# Power.net
KiCad netlist of a schematic drawn in Altium Designer
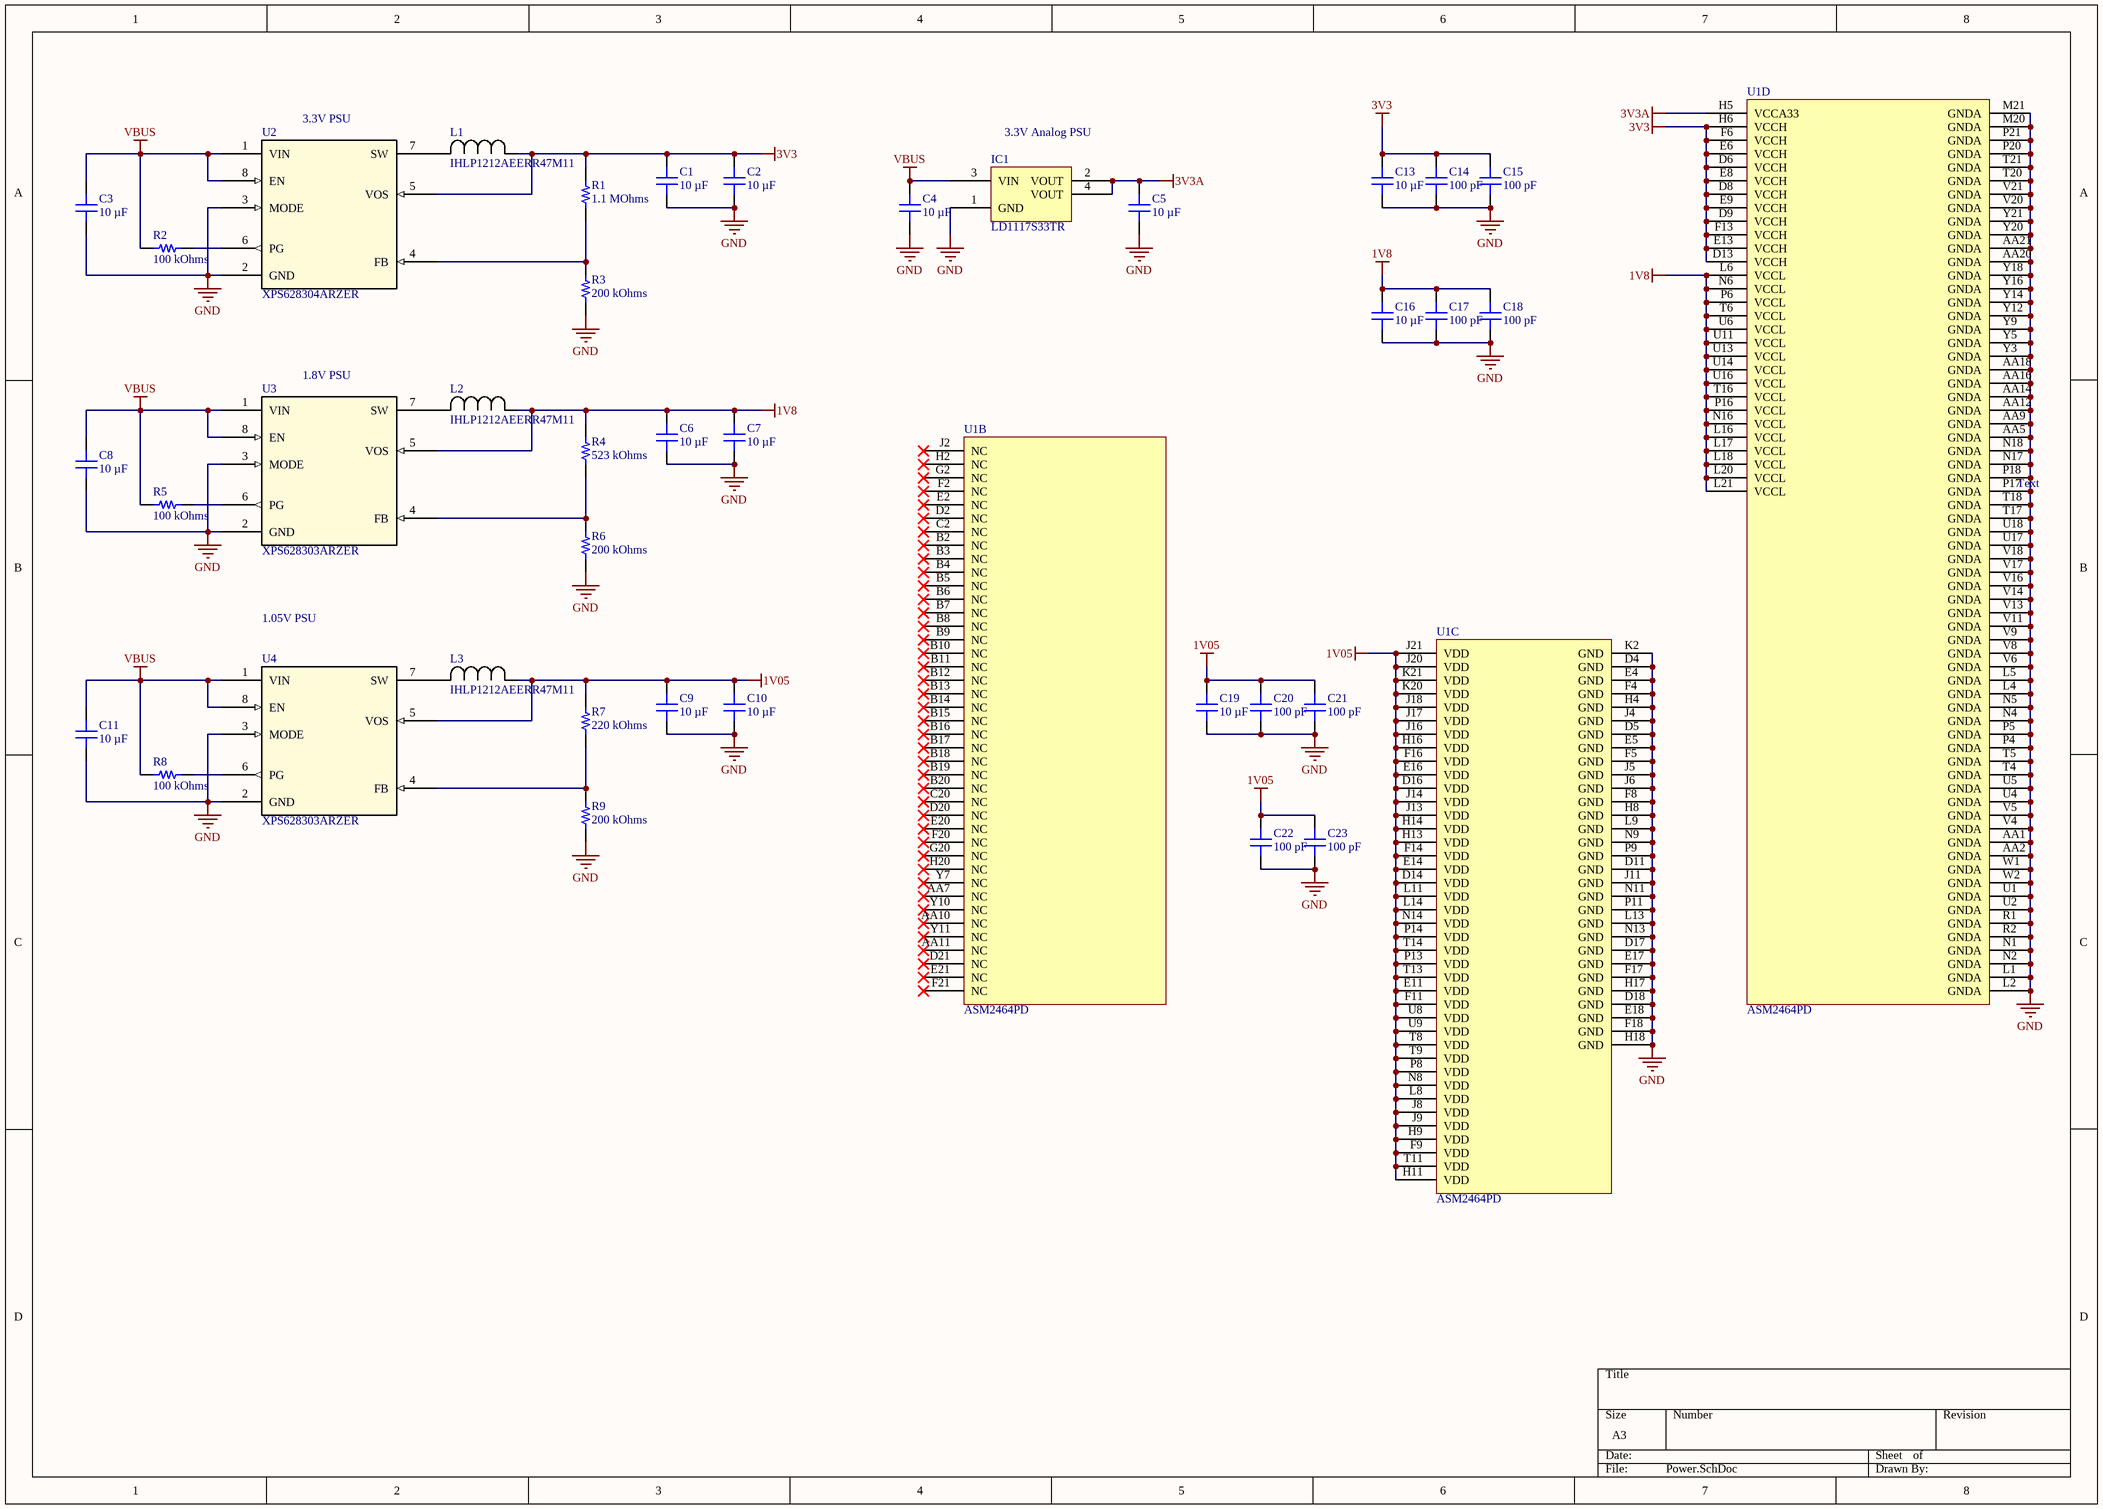
[diagram p0: Power.SchDoc]

(export (version "E")
  (design (tool "Eeschema 10.0.6"))
  (components
    (comp (ref "C1")
      (value "10 µF")
      (footprint "CAP 0805_2012")
      (description "CAP CER 10UF 16V X5R 0805")
      (fields
        (field (name "PART NUMBER") "GRM21BR61C106ME15L")
        (field (name "MANUFACTURER") "Murata Electronics")
      )
      (libsource (lib "Celestial Altium Library - altium_library") (part "Capacitor"))
    )
    (comp (ref "C2")
      (value "10 µF")
      (footprint "CAP 0805_2012")
      (description "CAP CER 10UF 16V X5R 0805")
      (fields
        (field (name "PART NUMBER") "GRM21BR61C106ME15L")
        (field (name "MANUFACTURER") "Murata Electronics")
      )
      (libsource (lib "Celestial Altium Library - altium_library") (part "Capacitor"))
    )
    (comp (ref "C3")
      (value "10 µF")
      (footprint "CAP 0805_2012")
      (description "CAP CER 10UF 16V X5R 0805")
      (fields
        (field (name "PART NUMBER") "GRM21BR61C106ME15L")
        (field (name "MANUFACTURER") "Murata Electronics")
      )
      (libsource (lib "Celestial Altium Library - altium_library") (part "Capacitor"))
    )
    (comp (ref "C4")
      (value "10 µF")
      (footprint "CAP 0805_2012")
      (description "CAP CER 10UF 16V X5R 0805")
      (fields
        (field (name "PART NUMBER") "GRM21BR61C106ME15L")
        (field (name "MANUFACTURER") "Murata Electronics")
      )
      (libsource (lib "Celestial Altium Library - altium_library") (part "Capacitor"))
    )
    (comp (ref "C5")
      (value "10 µF")
      (footprint "CAP 0805_2012")
      (description "CAP CER 10UF 16V X5R 0805")
      (fields
        (field (name "PART NUMBER") "GRM21BR61C106ME15L")
        (field (name "MANUFACTURER") "Murata Electronics")
      )
      (libsource (lib "Celestial Altium Library - altium_library") (part "Capacitor"))
    )
    (comp (ref "C6")
      (value "10 µF")
      (footprint "CAP 0805_2012")
      (description "CAP CER 10UF 16V X5R 0805")
      (fields
        (field (name "PART NUMBER") "GRM21BR61C106ME15L")
        (field (name "MANUFACTURER") "Murata Electronics")
      )
      (libsource (lib "Celestial Altium Library - altium_library") (part "Capacitor"))
    )
    (comp (ref "C7")
      (value "10 µF")
      (footprint "CAP 0805_2012")
      (description "CAP CER 10UF 16V X5R 0805")
      (fields
        (field (name "PART NUMBER") "GRM21BR61C106ME15L")
        (field (name "MANUFACTURER") "Murata Electronics")
      )
      (libsource (lib "Celestial Altium Library - altium_library") (part "Capacitor"))
    )
    (comp (ref "C8")
      (value "10 µF")
      (footprint "CAP 0805_2012")
      (description "CAP CER 10UF 16V X5R 0805")
      (fields
        (field (name "PART NUMBER") "GRM21BR61C106ME15L")
        (field (name "MANUFACTURER") "Murata Electronics")
      )
      (libsource (lib "Celestial Altium Library - altium_library") (part "Capacitor"))
    )
    (comp (ref "C9")
      (value "10 µF")
      (footprint "CAP 0805_2012")
      (description "CAP CER 10UF 16V X5R 0805")
      (fields
        (field (name "PART NUMBER") "GRM21BR61C106ME15L")
        (field (name "MANUFACTURER") "Murata Electronics")
      )
      (libsource (lib "Celestial Altium Library - altium_library") (part "Capacitor"))
    )
    (comp (ref "C10")
      (value "10 µF")
      (footprint "CAP 0805_2012")
      (description "CAP CER 10UF 16V X5R 0805")
      (fields
        (field (name "PART NUMBER") "GRM21BR61C106ME15L")
        (field (name "MANUFACTURER") "Murata Electronics")
      )
      (libsource (lib "Celestial Altium Library - altium_library") (part "Capacitor"))
    )
    (comp (ref "C11")
      (value "10 µF")
      (footprint "CAP 0805_2012")
      (description "CAP CER 10UF 16V X5R 0805")
      (fields
        (field (name "PART NUMBER") "GRM21BR61C106ME15L")
        (field (name "MANUFACTURER") "Murata Electronics")
      )
      (libsource (lib "Celestial Altium Library - altium_library") (part "Capacitor"))
    )
    (comp (ref "C13")
      (value "10 µF")
      (footprint "CAP 0805_2012")
      (description "CAP CER 10UF 16V X5R 0805")
      (fields
        (field (name "PART NUMBER") "GRM21BR61C106ME15L")
        (field (name "MANUFACTURER") "Murata Electronics")
      )
      (libsource (lib "Celestial Altium Library - altium_library") (part "Capacitor"))
    )
    (comp (ref "C14")
      (value "100 pF")
      (footprint "CAP 0603_1608")
      (description "CAP CER 100PF 100V X8G 0603")
      (fields
        (field (name "PART NUMBER") "GCM1885G2A101JA16D")
        (field (name "MANUFACTURER") "Murata Electronics")
      )
      (libsource (lib "Celestial Altium Library - altium_library") (part "Capacitor"))
    )
    (comp (ref "C15")
      (value "100 pF")
      (footprint "CAP 0603_1608")
      (description "CAP CER 100PF 100V X8G 0603")
      (fields
        (field (name "PART NUMBER") "GCM1885G2A101JA16D")
        (field (name "MANUFACTURER") "Murata Electronics")
      )
      (libsource (lib "Celestial Altium Library - altium_library") (part "Capacitor"))
    )
    (comp (ref "C16")
      (value "10 µF")
      (footprint "CAP 0805_2012")
      (description "CAP CER 10UF 16V X5R 0805")
      (fields
        (field (name "PART NUMBER") "GRM21BR61C106ME15L")
        (field (name "MANUFACTURER") "Murata Electronics")
      )
      (libsource (lib "Celestial Altium Library - altium_library") (part "Capacitor"))
    )
    (comp (ref "C17")
      (value "100 pF")
      (footprint "CAP 0603_1608")
      (description "CAP CER 100PF 100V X8G 0603")
      (fields
        (field (name "PART NUMBER") "GCM1885G2A101JA16D")
        (field (name "MANUFACTURER") "Murata Electronics")
      )
      (libsource (lib "Celestial Altium Library - altium_library") (part "Capacitor"))
    )
    (comp (ref "C18")
      (value "100 pF")
      (footprint "CAP 0603_1608")
      (description "CAP CER 100PF 100V X8G 0603")
      (fields
        (field (name "PART NUMBER") "GCM1885G2A101JA16D")
        (field (name "MANUFACTURER") "Murata Electronics")
      )
      (libsource (lib "Celestial Altium Library - altium_library") (part "Capacitor"))
    )
    (comp (ref "C19")
      (value "10 µF")
      (footprint "CAP 0805_2012")
      (description "CAP CER 10UF 16V X5R 0805")
      (fields
        (field (name "PART NUMBER") "GRM21BR61C106ME15L")
        (field (name "MANUFACTURER") "Murata Electronics")
      )
      (libsource (lib "Celestial Altium Library - altium_library") (part "Capacitor"))
    )
    (comp (ref "C20")
      (value "100 pF")
      (footprint "CAP 0603_1608")
      (description "CAP CER 100PF 100V X8G 0603")
      (fields
        (field (name "PART NUMBER") "GCM1885G2A101JA16D")
        (field (name "MANUFACTURER") "Murata Electronics")
      )
      (libsource (lib "Celestial Altium Library - altium_library") (part "Capacitor"))
    )
    (comp (ref "C21")
      (value "100 pF")
      (footprint "CAP 0603_1608")
      (description "CAP CER 100PF 100V X8G 0603")
      (fields
        (field (name "PART NUMBER") "GCM1885G2A101JA16D")
        (field (name "MANUFACTURER") "Murata Electronics")
      )
      (libsource (lib "Celestial Altium Library - altium_library") (part "Capacitor"))
    )
    (comp (ref "C22")
      (value "100 pF")
      (footprint "CAP 0603_1608")
      (description "CAP CER 100PF 100V X8G 0603")
      (fields
        (field (name "PART NUMBER") "GCM1885G2A101JA16D")
        (field (name "MANUFACTURER") "Murata Electronics")
      )
      (libsource (lib "Celestial Altium Library - altium_library") (part "Capacitor"))
    )
    (comp (ref "C23")
      (value "100 pF")
      (footprint "CAP 0603_1608")
      (description "CAP CER 100PF 100V X8G 0603")
      (fields
        (field (name "PART NUMBER") "GCM1885G2A101JA16D")
        (field (name "MANUFACTURER") "Murata Electronics")
      )
      (libsource (lib "Celestial Altium Library - altium_library") (part "Capacitor"))
    )
    (comp (ref "IC1")
      (value "LD1117S33TR")
      (footprint "ST SOT-223")
      (description "IC REG LINEAR 3.3V 800MA SOT223")
      (fields (field (name "MANUFACTURER") "STMicroelectronics"))
      (libsource (lib "Celestial Altium Library - altium_library") (part "ST LD1117"))
    )
    (comp (ref "L1")
      (value "IHLP1212AEERR47M11")
      (footprint "IND_IHLP-1212AE_VIS")
      (description "No Description Available")
      (libsource (lib "IHLP1212AEERR47M11") (part "IHLP1212AEERR47M11"))
    )
    (comp (ref "L2")
      (value "IHLP1212AEERR47M11")
      (footprint "IND_IHLP-1212AE_VIS")
      (description "No Description Available")
      (libsource (lib "IHLP1212AEERR47M11") (part "IHLP1212AEERR47M11"))
    )
    (comp (ref "L3")
      (value "IHLP1212AEERR47M11")
      (footprint "IND_IHLP-1212AE_VIS")
      (description "No Description Available")
      (libsource (lib "IHLP1212AEERR47M11") (part "IHLP1212AEERR47M11"))
    )
    (comp (ref "R1")
      (value "1.1 MOhms")
      (footprint "RES 0805_2012")
      (description "RES SMD 1.1M OHM 5% 1/8W 0805")
      (fields
        (field (name "PART NUMBER") "ERJ-6GEYJ115V")
        (field (name "MANUFACTURER") "Panasonic Electronic Components")
      )
      (libsource (lib "Celestial Altium Library - altium_library") (part "Resistor"))
    )
    (comp (ref "R2")
      (value "100 kOhms")
      (footprint "RES 0805_2012")
      (description "RES SMD 100K OHM 1% 1/8W 0805")
      (fields (field (name "PART NUMBER") "CRCW0805100KFKEA") (field (name "MANUFACTURER") "Vishay Dale"))
      (libsource (lib "Celestial Altium Library - altium_library") (part "Resistor"))
    )
    (comp (ref "R3")
      (value "200 kOhms")
      (footprint "RES 0805_2012")
      (description "RES SMD 200K OHM 5% 1/8W 0805")
      (fields
        (field (name "PART NUMBER") "ERJ-6GEYJ204V")
        (field (name "MANUFACTURER") "Panasonic Electronic Components")
      )
      (libsource (lib "Celestial Altium Library - altium_library") (part "Resistor"))
    )
    (comp (ref "R4")
      (value "523 kOhms")
      (footprint "RES 0805_2012")
      (description "RES SMD 523K OHM 1% 1/8W 0805")
      (fields
        (field (name "PART NUMBER") "ERJ-6ENF5233V")
        (field (name "MANUFACTURER") "Panasonic Electronic Components")
      )
      (libsource (lib "Celestial Altium Library - altium_library") (part "Resistor"))
    )
    (comp (ref "R5")
      (value "100 kOhms")
      (footprint "RES 0805_2012")
      (description "RES SMD 100K OHM 1% 1/8W 0805")
      (fields (field (name "PART NUMBER") "CRCW0805100KFKEA") (field (name "MANUFACTURER") "Vishay Dale"))
      (libsource (lib "Celestial Altium Library - altium_library") (part "Resistor"))
    )
    (comp (ref "R6")
      (value "200 kOhms")
      (footprint "RES 0805_2012")
      (description "RES SMD 200K OHM 5% 1/8W 0805")
      (fields
        (field (name "PART NUMBER") "ERJ-6GEYJ204V")
        (field (name "MANUFACTURER") "Panasonic Electronic Components")
      )
      (libsource (lib "Celestial Altium Library - altium_library") (part "Resistor"))
    )
    (comp (ref "R7")
      (value "220 kOhms")
      (footprint "RES 0805_2012")
      (description "RES SMD 220K OHM 5% 1/8W 0805")
      (fields
        (field (name "PART NUMBER") "ERJ-6GEYJ224V")
        (field (name "MANUFACTURER") "Panasonic Electronic Components")
      )
      (libsource (lib "Celestial Altium Library - altium_library") (part "Resistor"))
    )
    (comp (ref "R8")
      (value "100 kOhms")
      (footprint "RES 0805_2012")
      (description "RES SMD 100K OHM 1% 1/8W 0805")
      (fields (field (name "PART NUMBER") "CRCW0805100KFKEA") (field (name "MANUFACTURER") "Vishay Dale"))
      (libsource (lib "Celestial Altium Library - altium_library") (part "Resistor"))
    )
    (comp (ref "R9")
      (value "200 kOhms")
      (footprint "RES 0805_2012")
      (description "RES SMD 200K OHM 5% 1/8W 0805")
      (fields
        (field (name "PART NUMBER") "ERJ-6GEYJ204V")
        (field (name "MANUFACTURER") "Panasonic Electronic Components")
      )
      (libsource (lib "Celestial Altium Library - altium_library") (part "Resistor"))
    )
    (comp (ref "U1")
      (value "ASM2464PD")
      (footprint "BGA273C46P21X21_1000X1000X98_2")
      (libsource (lib " JS") (part "ASM2464PD"))
    )
    (comp (ref "U2")
      (value "XPS628304ARZER")
      (footprint "WQFN-HR8_RZE_TEX")
      (description "No Description Available")
      (libsource (lib "XPS628303ARZER") (part "XPS628304ARZER"))
    )
    (comp (ref "U3")
      (value "XPS628303ARZER")
      (footprint "WQFN-HR8_RZE_TEX")
      (description "No Description Available")
      (libsource (lib "XPS628303ARZER") (part "XPS628303ARZER"))
    )
    (comp (ref "U4")
      (value "XPS628303ARZER")
      (footprint "WQFN-HR8_RZE_TEX")
      (description "No Description Available")
      (libsource (lib "XPS628303ARZER") (part "XPS628303ARZER"))
    )
  )
  (nets
    (net (code "1") (name "1V05") (class "Default")
      (node (ref "C10") (pin "2") (pinfunction "2_2") (pintype "passive"))
      (node (ref "C19") (pin "2") (pinfunction "2_2") (pintype "passive"))
      (node (ref "C20") (pin "2") (pinfunction "2_2") (pintype "passive"))
      (node (ref "C21") (pin "2") (pinfunction "2_2") (pintype "passive"))
      (node (ref "C22") (pin "2") (pinfunction "2_2") (pintype "passive"))
      (node (ref "C23") (pin "2") (pinfunction "2_2") (pintype "passive"))
      (node (ref "C9") (pin "2") (pinfunction "2_2") (pintype "passive"))
      (node (ref "L3") (pin "1") (pinfunction "1_1") (pintype "passive"))
      (node (ref "R7") (pin "2") (pinfunction "2_2") (pintype "passive"))
      (node (ref "U1") (pin "D14") (pinfunction "VDD_D14") (pintype "power_in"))
      (node (ref "U1") (pin "D16") (pinfunction "VDD_D16") (pintype "power_in"))
      (node (ref "U1") (pin "E11") (pinfunction "VDD_E11") (pintype "power_in"))
      (node (ref "U1") (pin "E14") (pinfunction "VDD_E14") (pintype "power_in"))
      (node (ref "U1") (pin "E16") (pinfunction "VDD_E16") (pintype "power_in"))
      (node (ref "U1") (pin "F11") (pinfunction "VDD_F11") (pintype "power_in"))
      (node (ref "U1") (pin "F14") (pinfunction "VDD_F14") (pintype "power_in"))
      (node (ref "U1") (pin "F16") (pinfunction "VDD_F16") (pintype "power_in"))
      (node (ref "U1") (pin "F9") (pinfunction "VDD_F9") (pintype "power_in"))
      (node (ref "U1") (pin "H11") (pinfunction "VDD_H11") (pintype "power_in"))
      (node (ref "U1") (pin "H13") (pinfunction "VDD_H13") (pintype "power_in"))
      (node (ref "U1") (pin "H14") (pinfunction "VDD_H14") (pintype "power_in"))
      (node (ref "U1") (pin "H16") (pinfunction "VDD_H16") (pintype "power_in"))
      (node (ref "U1") (pin "H9") (pinfunction "VDD_H9") (pintype "power_in"))
      (node (ref "U1") (pin "J13") (pinfunction "VDD_J13") (pintype "power_in"))
      (node (ref "U1") (pin "J14") (pinfunction "VDD_J14") (pintype "power_in"))
      (node (ref "U1") (pin "J16") (pinfunction "VDD_J16") (pintype "power_in"))
      (node (ref "U1") (pin "J17") (pinfunction "VDD_J17") (pintype "power_in"))
      (node (ref "U1") (pin "J18") (pinfunction "VDD_J18") (pintype "power_in"))
      (node (ref "U1") (pin "J20") (pinfunction "VDD_J20") (pintype "power_in"))
      (node (ref "U1") (pin "J21") (pinfunction "VDD_J21") (pintype "power_in"))
      (node (ref "U1") (pin "J8") (pinfunction "VDD_J8") (pintype "power_in"))
      (node (ref "U1") (pin "J9") (pinfunction "VDD_J9") (pintype "power_in"))
      (node (ref "U1") (pin "K20") (pinfunction "VDD_K20") (pintype "power_in"))
      (node (ref "U1") (pin "K21") (pinfunction "VDD_K21") (pintype "power_in"))
      (node (ref "U1") (pin "L11") (pinfunction "VDD_L11") (pintype "power_in"))
      (node (ref "U1") (pin "L14") (pinfunction "VDD_L14") (pintype "power_in"))
      (node (ref "U1") (pin "L8") (pinfunction "VDD_L8") (pintype "power_in"))
      (node (ref "U1") (pin "N14") (pinfunction "VDD_N14") (pintype "power_in"))
      (node (ref "U1") (pin "N8") (pinfunction "VDD_N8") (pintype "power_in"))
      (node (ref "U1") (pin "P13") (pinfunction "VDD_P13") (pintype "power_in"))
      (node (ref "U1") (pin "P14") (pinfunction "VDD_P14") (pintype "power_in"))
      (node (ref "U1") (pin "P8") (pinfunction "VDD_P8") (pintype "power_in"))
      (node (ref "U1") (pin "T11") (pinfunction "VDD_T11") (pintype "power_in"))
      (node (ref "U1") (pin "T13") (pinfunction "VDD_T13") (pintype "power_in"))
      (node (ref "U1") (pin "T14") (pinfunction "VDD_T14") (pintype "power_in"))
      (node (ref "U1") (pin "T8") (pinfunction "VDD_T8") (pintype "power_in"))
      (node (ref "U1") (pin "T9") (pinfunction "VDD_T9") (pintype "power_in"))
      (node (ref "U1") (pin "U8") (pinfunction "VDD_U8") (pintype "power_in"))
      (node (ref "U1") (pin "U9") (pinfunction "VDD_U9") (pintype "power_in"))
      (node (ref "U4") (pin "5") (pinfunction "VOS_5") (pintype "input"))
    )
    (net (code "2") (name "1V8") (class "Default")
      (node (ref "C16") (pin "2") (pinfunction "2_2") (pintype "passive"))
      (node (ref "C17") (pin "2") (pinfunction "2_2") (pintype "passive"))
      (node (ref "C18") (pin "2") (pinfunction "2_2") (pintype "passive"))
      (node (ref "C6") (pin "2") (pinfunction "2_2") (pintype "passive"))
      (node (ref "C7") (pin "2") (pinfunction "2_2") (pintype "passive"))
      (node (ref "L2") (pin "1") (pinfunction "1_1") (pintype "passive"))
      (node (ref "R4") (pin "2") (pinfunction "2_2") (pintype "passive"))
      (node (ref "U1") (pin "L16") (pinfunction "VCCL_L16") (pintype "power_in"))
      (node (ref "U1") (pin "L17") (pinfunction "VCCL_L17") (pintype "power_in"))
      (node (ref "U1") (pin "L18") (pinfunction "VCCL_L18") (pintype "power_in"))
      (node (ref "U1") (pin "L20") (pinfunction "VCCL_L20") (pintype "power_in"))
      (node (ref "U1") (pin "L21") (pinfunction "VCCL_L21") (pintype "power_in"))
      (node (ref "U1") (pin "L6") (pinfunction "VCCL_L6") (pintype "power_in"))
      (node (ref "U1") (pin "N16") (pinfunction "VCCL_N16") (pintype "power_in"))
      (node (ref "U1") (pin "N6") (pinfunction "VCCL_N6") (pintype "power_in"))
      (node (ref "U1") (pin "P16") (pinfunction "VCCL_P16") (pintype "power_in"))
      (node (ref "U1") (pin "P6") (pinfunction "VCCL_P6") (pintype "power_in"))
      (node (ref "U1") (pin "T16") (pinfunction "VCCL_T16") (pintype "power_in"))
      (node (ref "U1") (pin "T6") (pinfunction "VCCL_T6") (pintype "power_in"))
      (node (ref "U1") (pin "U11") (pinfunction "VCCL_U11") (pintype "power_in"))
      (node (ref "U1") (pin "U13") (pinfunction "VCCL_U13") (pintype "power_in"))
      (node (ref "U1") (pin "U14") (pinfunction "VCCL_U14") (pintype "power_in"))
      (node (ref "U1") (pin "U16") (pinfunction "VCCL_U16") (pintype "power_in"))
      (node (ref "U1") (pin "U6") (pinfunction "VCCL_U6") (pintype "power_in"))
      (node (ref "U3") (pin "5") (pinfunction "VOS_5") (pintype "input"))
    )
    (net (code "3") (name "3V3") (class "Default")
      (node (ref "C1") (pin "2") (pinfunction "2_2") (pintype "passive"))
      (node (ref "C13") (pin "2") (pinfunction "2_2") (pintype "passive"))
      (node (ref "C14") (pin "2") (pinfunction "2_2") (pintype "passive"))
      (node (ref "C15") (pin "2") (pinfunction "2_2") (pintype "passive"))
      (node (ref "C2") (pin "2") (pinfunction "2_2") (pintype "passive"))
      (node (ref "L1") (pin "1") (pinfunction "1_1") (pintype "passive"))
      (node (ref "R1") (pin "2") (pinfunction "2_2") (pintype "passive"))
      (node (ref "U1") (pin "D13") (pinfunction "VCCH_D13") (pintype "power_in"))
      (node (ref "U1") (pin "D6") (pinfunction "VCCH_D6") (pintype "power_in"))
      (node (ref "U1") (pin "D8") (pinfunction "VCCH_D8") (pintype "power_in"))
      (node (ref "U1") (pin "D9") (pinfunction "VCCH_D9") (pintype "power_in"))
      (node (ref "U1") (pin "E13") (pinfunction "VCCH_E13") (pintype "power_in"))
      (node (ref "U1") (pin "E6") (pinfunction "VCCH_E6") (pintype "power_in"))
      (node (ref "U1") (pin "E8") (pinfunction "VCCH_E8") (pintype "power_in"))
      (node (ref "U1") (pin "E9") (pinfunction "VCCH_E9") (pintype "power_in"))
      (node (ref "U1") (pin "F13") (pinfunction "VCCH_F13") (pintype "power_in"))
      (node (ref "U1") (pin "F6") (pinfunction "VCCH_F6") (pintype "power_in"))
      (node (ref "U1") (pin "H6") (pinfunction "VCCH_H6") (pintype "power_in"))
      (node (ref "U2") (pin "5") (pinfunction "VOS_5") (pintype "input"))
    )
    (net (code "4") (name "3V3A") (class "Default")
      (node (ref "C5") (pin "2") (pinfunction "2_2") (pintype "passive"))
      (node (ref "IC1") (pin "2") (pinfunction "VOUT_2") (pintype "passive"))
      (node (ref "IC1") (pin "4") (pinfunction "VOUT_4") (pintype "passive"))
      (node (ref "U1") (pin "H5") (pinfunction "VCCA33_H5") (pintype "power_in"))
    )
    (net (code "5") (name "GND") (class "Default")
      (node (ref "C1") (pin "1") (pinfunction "1_1") (pintype "passive"))
      (node (ref "C10") (pin "1") (pinfunction "1_1") (pintype "passive"))
      (node (ref "C11") (pin "1") (pinfunction "1_1") (pintype "passive"))
      (node (ref "C13") (pin "1") (pinfunction "1_1") (pintype "passive"))
      (node (ref "C14") (pin "1") (pinfunction "1_1") (pintype "passive"))
      (node (ref "C15") (pin "1") (pinfunction "1_1") (pintype "passive"))
      (node (ref "C16") (pin "1") (pinfunction "1_1") (pintype "passive"))
      (node (ref "C17") (pin "1") (pinfunction "1_1") (pintype "passive"))
      (node (ref "C18") (pin "1") (pinfunction "1_1") (pintype "passive"))
      (node (ref "C19") (pin "1") (pinfunction "1_1") (pintype "passive"))
      (node (ref "C2") (pin "1") (pinfunction "1_1") (pintype "passive"))
      (node (ref "C20") (pin "1") (pinfunction "1_1") (pintype "passive"))
      (node (ref "C21") (pin "1") (pinfunction "1_1") (pintype "passive"))
      (node (ref "C22") (pin "1") (pinfunction "1_1") (pintype "passive"))
      (node (ref "C23") (pin "1") (pinfunction "1_1") (pintype "passive"))
      (node (ref "C3") (pin "1") (pinfunction "1_1") (pintype "passive"))
      (node (ref "C4") (pin "1") (pinfunction "1_1") (pintype "passive"))
      (node (ref "C5") (pin "1") (pinfunction "1_1") (pintype "passive"))
      (node (ref "C6") (pin "1") (pinfunction "1_1") (pintype "passive"))
      (node (ref "C7") (pin "1") (pinfunction "1_1") (pintype "passive"))
      (node (ref "C8") (pin "1") (pinfunction "1_1") (pintype "passive"))
      (node (ref "C9") (pin "1") (pinfunction "1_1") (pintype "passive"))
      (node (ref "IC1") (pin "1") (pinfunction "GND_1") (pintype "passive"))
      (node (ref "R3") (pin "1") (pinfunction "1_1") (pintype "passive"))
      (node (ref "R6") (pin "1") (pinfunction "1_1") (pintype "passive"))
      (node (ref "R9") (pin "1") (pinfunction "1_1") (pintype "passive"))
      (node (ref "U1") (pin "AA1") (pinfunction "GNDA_AA1") (pintype "power_in"))
      (node (ref "U1") (pin "AA12") (pinfunction "GNDA_AA12") (pintype "power_in"))
      (node (ref "U1") (pin "AA14") (pinfunction "GNDA_AA14") (pintype "power_in"))
      (node (ref "U1") (pin "AA16") (pinfunction "GNDA_AA16") (pintype "power_in"))
      (node (ref "U1") (pin "AA18") (pinfunction "GNDA_AA18") (pintype "power_in"))
      (node (ref "U1") (pin "AA2") (pinfunction "GNDA_AA2") (pintype "power_in"))
      (node (ref "U1") (pin "AA20") (pinfunction "GNDA_AA20") (pintype "power_in"))
      (node (ref "U1") (pin "AA21") (pinfunction "GNDA_AA21") (pintype "power_in"))
      (node (ref "U1") (pin "AA5") (pinfunction "GNDA_AA5") (pintype "power_in"))
      (node (ref "U1") (pin "AA9") (pinfunction "GNDA_AA9") (pintype "power_in"))
      (node (ref "U1") (pin "D11") (pinfunction "GND_D11") (pintype "power_in"))
      (node (ref "U1") (pin "D17") (pinfunction "GND_D17") (pintype "power_in"))
      (node (ref "U1") (pin "D18") (pinfunction "GND_D18") (pintype "power_in"))
      (node (ref "U1") (pin "D4") (pinfunction "GND_D4") (pintype "power_in"))
      (node (ref "U1") (pin "D5") (pinfunction "GND_D5") (pintype "power_in"))
      (node (ref "U1") (pin "E17") (pinfunction "GND_E17") (pintype "power_in"))
      (node (ref "U1") (pin "E18") (pinfunction "GND_E18") (pintype "power_in"))
      (node (ref "U1") (pin "E4") (pinfunction "GND_E4") (pintype "power_in"))
      (node (ref "U1") (pin "E5") (pinfunction "GND_E5") (pintype "power_in"))
      (node (ref "U1") (pin "F17") (pinfunction "GND_F17") (pintype "power_in"))
      (node (ref "U1") (pin "F18") (pinfunction "GND_F18") (pintype "power_in"))
      (node (ref "U1") (pin "F4") (pinfunction "GND_F4") (pintype "power_in"))
      (node (ref "U1") (pin "F5") (pinfunction "GND_F5") (pintype "power_in"))
      (node (ref "U1") (pin "F8") (pinfunction "GND_F8") (pintype "power_in"))
      (node (ref "U1") (pin "H17") (pinfunction "GND_H17") (pintype "power_in"))
      (node (ref "U1") (pin "H18") (pinfunction "GND_H18") (pintype "power_in"))
      (node (ref "U1") (pin "H4") (pinfunction "GND_H4") (pintype "power_in"))
      (node (ref "U1") (pin "H8") (pinfunction "GND_H8") (pintype "power_in"))
      (node (ref "U1") (pin "J11") (pinfunction "GND_J11") (pintype "power_in"))
      (node (ref "U1") (pin "J4") (pinfunction "GND_J4") (pintype "power_in"))
      (node (ref "U1") (pin "J5") (pinfunction "GND_J5") (pintype "power_in"))
      (node (ref "U1") (pin "J6") (pinfunction "GND_J6") (pintype "power_in"))
      (node (ref "U1") (pin "K2") (pinfunction "GND_K2") (pintype "power_in"))
      (node (ref "U1") (pin "L1") (pinfunction "GNDA_L1") (pintype "power_in"))
      (node (ref "U1") (pin "L13") (pinfunction "GND_L13") (pintype "power_in"))
      (node (ref "U1") (pin "L2") (pinfunction "GNDA_L2") (pintype "power_in"))
      (node (ref "U1") (pin "L4") (pinfunction "GNDA_L4") (pintype "power_in"))
      (node (ref "U1") (pin "L5") (pinfunction "GNDA_L5") (pintype "power_in"))
      (node (ref "U1") (pin "L9") (pinfunction "GND_L9") (pintype "power_in"))
      (node (ref "U1") (pin "M20") (pinfunction "GNDA_M20") (pintype "power_in"))
      (node (ref "U1") (pin "M21") (pinfunction "GNDA_M21") (pintype "power_in"))
      (node (ref "U1") (pin "N1") (pinfunction "GNDA_N1") (pintype "power_in"))
      (node (ref "U1") (pin "N11") (pinfunction "GND_N11") (pintype "power_in"))
      (node (ref "U1") (pin "N13") (pinfunction "GND_N13") (pintype "power_in"))
      (node (ref "U1") (pin "N17") (pinfunction "GNDA_N17") (pintype "power_in"))
      (node (ref "U1") (pin "N18") (pinfunction "GNDA_N18") (pintype "power_in"))
      (node (ref "U1") (pin "N2") (pinfunction "GNDA_N2") (pintype "power_in"))
      (node (ref "U1") (pin "N4") (pinfunction "GNDA_N4") (pintype "power_in"))
      (node (ref "U1") (pin "N5") (pinfunction "GNDA_N5") (pintype "power_in"))
      (node (ref "U1") (pin "N9") (pinfunction "GND_N9") (pintype "power_in"))
      (node (ref "U1") (pin "P11") (pinfunction "GND_P11") (pintype "power_in"))
      (node (ref "U1") (pin "P17") (pinfunction "GNDA_P17") (pintype "power_in"))
      (node (ref "U1") (pin "P18") (pinfunction "GNDA_P18") (pintype "power_in"))
      (node (ref "U1") (pin "P20") (pinfunction "GNDA_P20") (pintype "power_in"))
      (node (ref "U1") (pin "P21") (pinfunction "GNDA_P21") (pintype "power_in"))
      (node (ref "U1") (pin "P4") (pinfunction "GNDA_P4") (pintype "power_in"))
      (node (ref "U1") (pin "P5") (pinfunction "GNDA_P5") (pintype "power_in"))
      (node (ref "U1") (pin "P9") (pinfunction "GND_P9") (pintype "power_in"))
      (node (ref "U1") (pin "R1") (pinfunction "GNDA_R1") (pintype "power_in"))
      (node (ref "U1") (pin "R2") (pinfunction "GNDA_R2") (pintype "power_in"))
      (node (ref "U1") (pin "T17") (pinfunction "GNDA_T17") (pintype "power_in"))
      (node (ref "U1") (pin "T18") (pinfunction "GNDA_T18") (pintype "power_in"))
      (node (ref "U1") (pin "T20") (pinfunction "GNDA_T20") (pintype "power_in"))
      (node (ref "U1") (pin "T21") (pinfunction "GNDA_T21") (pintype "power_in"))
      (node (ref "U1") (pin "T4") (pinfunction "GNDA_T4") (pintype "power_in"))
      (node (ref "U1") (pin "T5") (pinfunction "GNDA_T5") (pintype "power_in"))
      (node (ref "U1") (pin "U1") (pinfunction "GNDA_U1") (pintype "power_in"))
      (node (ref "U1") (pin "U17") (pinfunction "GNDA_U17") (pintype "power_in"))
      (node (ref "U1") (pin "U18") (pinfunction "GNDA_U18") (pintype "power_in"))
      (node (ref "U1") (pin "U2") (pinfunction "GNDA_U2") (pintype "power_in"))
      (node (ref "U1") (pin "U4") (pinfunction "GNDA_U4") (pintype "power_in"))
      (node (ref "U1") (pin "U5") (pinfunction "GNDA_U5") (pintype "power_in"))
      (node (ref "U1") (pin "V11") (pinfunction "GNDA_V11") (pintype "power_in"))
      (node (ref "U1") (pin "V13") (pinfunction "GNDA_V13") (pintype "power_in"))
      (node (ref "U1") (pin "V14") (pinfunction "GNDA_V14") (pintype "power_in"))
      (node (ref "U1") (pin "V16") (pinfunction "GNDA_V16") (pintype "power_in"))
      (node (ref "U1") (pin "V17") (pinfunction "GNDA_V17") (pintype "power_in"))
      (node (ref "U1") (pin "V18") (pinfunction "GNDA_V18") (pintype "power_in"))
      (node (ref "U1") (pin "V20") (pinfunction "GNDA_V20") (pintype "power_in"))
      (node (ref "U1") (pin "V21") (pinfunction "GNDA_V21") (pintype "power_in"))
      (node (ref "U1") (pin "V4") (pinfunction "GNDA_V4") (pintype "power_in"))
      (node (ref "U1") (pin "V5") (pinfunction "GNDA_V5") (pintype "power_in"))
      (node (ref "U1") (pin "V6") (pinfunction "GNDA_V6") (pintype "power_in"))
      (node (ref "U1") (pin "V8") (pinfunction "GNDA_V8") (pintype "power_in"))
      (node (ref "U1") (pin "V9") (pinfunction "GNDA_V9") (pintype "power_in"))
      (node (ref "U1") (pin "W1") (pinfunction "GNDA_W1") (pintype "power_in"))
      (node (ref "U1") (pin "W2") (pinfunction "GNDA_W2") (pintype "power_in"))
      (node (ref "U1") (pin "Y12") (pinfunction "GNDA_Y12") (pintype "power_in"))
      (node (ref "U1") (pin "Y14") (pinfunction "GNDA_Y14") (pintype "power_in"))
      (node (ref "U1") (pin "Y16") (pinfunction "GNDA_Y16") (pintype "power_in"))
      (node (ref "U1") (pin "Y18") (pinfunction "GNDA_Y18") (pintype "power_in"))
      (node (ref "U1") (pin "Y20") (pinfunction "GNDA_Y20") (pintype "power_in"))
      (node (ref "U1") (pin "Y21") (pinfunction "GNDA_Y21") (pintype "power_in"))
      (node (ref "U1") (pin "Y3") (pinfunction "GNDA_Y3") (pintype "power_in"))
      (node (ref "U1") (pin "Y5") (pinfunction "GNDA_Y5") (pintype "power_in"))
      (node (ref "U1") (pin "Y9") (pinfunction "GNDA_Y9") (pintype "power_in"))
      (node (ref "U2") (pin "2") (pinfunction "GND_2") (pintype "power_in"))
      (node (ref "U2") (pin "3") (pinfunction "MODE_3") (pintype "input"))
      (node (ref "U3") (pin "2") (pinfunction "GND_2") (pintype "power_in"))
      (node (ref "U3") (pin "3") (pinfunction "MODE_3") (pintype "input"))
      (node (ref "U4") (pin "2") (pinfunction "GND_2") (pintype "power_in"))
      (node (ref "U4") (pin "3") (pinfunction "MODE_3") (pintype "input"))
    )
    (net (code "6") (name "Net-(U2-FB)") (class "Default")
      (node (ref "R1") (pin "1") (pinfunction "1_1") (pintype "passive"))
      (node (ref "R3") (pin "2") (pinfunction "2_2") (pintype "passive"))
      (node (ref "U2") (pin "4") (pinfunction "FB_4") (pintype "input"))
    )
    (net (code "7") (name "Net-(U2-PG)") (class "Default")
      (node (ref "R2") (pin "2") (pinfunction "2_2") (pintype "passive"))
      (node (ref "U2") (pin "6") (pinfunction "PG_6") (pintype "output"))
    )
    (net (code "8") (name "Net-(U2-SW)") (class "Default")
      (node (ref "L1") (pin "2") (pinfunction "2_2") (pintype "passive"))
      (node (ref "U2") (pin "7") (pinfunction "SW_7") (pintype "power_in"))
    )
    (net (code "9") (name "Net-(U3-FB)") (class "Default")
      (node (ref "R4") (pin "1") (pinfunction "1_1") (pintype "passive"))
      (node (ref "R6") (pin "2") (pinfunction "2_2") (pintype "passive"))
      (node (ref "U3") (pin "4") (pinfunction "FB_4") (pintype "input"))
    )
    (net (code "10") (name "Net-(U3-PG)") (class "Default")
      (node (ref "R5") (pin "2") (pinfunction "2_2") (pintype "passive"))
      (node (ref "U3") (pin "6") (pinfunction "PG_6") (pintype "output"))
    )
    (net (code "11") (name "Net-(U3-SW)") (class "Default")
      (node (ref "L2") (pin "2") (pinfunction "2_2") (pintype "passive"))
      (node (ref "U3") (pin "7") (pinfunction "SW_7") (pintype "power_in"))
    )
    (net (code "12") (name "Net-(U4-FB)") (class "Default")
      (node (ref "R7") (pin "1") (pinfunction "1_1") (pintype "passive"))
      (node (ref "R9") (pin "2") (pinfunction "2_2") (pintype "passive"))
      (node (ref "U4") (pin "4") (pinfunction "FB_4") (pintype "input"))
    )
    (net (code "13") (name "Net-(U4-PG)") (class "Default")
      (node (ref "R8") (pin "2") (pinfunction "2_2") (pintype "passive"))
      (node (ref "U4") (pin "6") (pinfunction "PG_6") (pintype "output"))
    )
    (net (code "14") (name "Net-(U4-SW)") (class "Default")
      (node (ref "L3") (pin "2") (pinfunction "2_2") (pintype "passive"))
      (node (ref "U4") (pin "7") (pinfunction "SW_7") (pintype "power_in"))
    )
    (net (code "15") (name "VBUS") (class "Default")
      (node (ref "C11") (pin "2") (pinfunction "2_2") (pintype "passive"))
      (node (ref "C3") (pin "2") (pinfunction "2_2") (pintype "passive"))
      (node (ref "C4") (pin "2") (pinfunction "2_2") (pintype "passive"))
      (node (ref "C8") (pin "2") (pinfunction "2_2") (pintype "passive"))
      (node (ref "IC1") (pin "3") (pinfunction "VIN_3") (pintype "passive"))
      (node (ref "R2") (pin "1") (pinfunction "1_1") (pintype "passive"))
      (node (ref "R5") (pin "1") (pinfunction "1_1") (pintype "passive"))
      (node (ref "R8") (pin "1") (pinfunction "1_1") (pintype "passive"))
      (node (ref "U2") (pin "1") (pinfunction "VIN_1") (pintype "power_in"))
      (node (ref "U2") (pin "8") (pinfunction "EN_8") (pintype "input"))
      (node (ref "U3") (pin "1") (pinfunction "VIN_1") (pintype "power_in"))
      (node (ref "U3") (pin "8") (pinfunction "EN_8") (pintype "input"))
      (node (ref "U4") (pin "1") (pinfunction "VIN_1") (pintype "power_in"))
      (node (ref "U4") (pin "8") (pinfunction "EN_8") (pintype "input"))
    )
    (net (code "16") (name "unconnected-(U1B-NC-PadAA7)") (class "Default")
      (node (ref "U1") (pin "AA7") (pinfunction "NC_AA7") (pintype "passive+no_connect"))
    )
    (net (code "17") (name "unconnected-(U1B-NC-PadAA10)") (class "Default")
      (node (ref "U1") (pin "AA10") (pinfunction "NC_AA10") (pintype "passive+no_connect"))
    )
    (net (code "18") (name "unconnected-(U1B-NC-PadAA11)") (class "Default")
      (node (ref "U1") (pin "AA11") (pinfunction "NC_AA11") (pintype "passive+no_connect"))
    )
    (net (code "19") (name "unconnected-(U1B-NC-PadB2)") (class "Default")
      (node (ref "U1") (pin "B2") (pinfunction "NC_B2") (pintype "passive+no_connect"))
    )
    (net (code "20") (name "unconnected-(U1B-NC-PadB3)") (class "Default")
      (node (ref "U1") (pin "B3") (pinfunction "NC_B3") (pintype "passive+no_connect"))
    )
    (net (code "21") (name "unconnected-(U1B-NC-PadB4)") (class "Default")
      (node (ref "U1") (pin "B4") (pinfunction "NC_B4") (pintype "passive+no_connect"))
    )
    (net (code "22") (name "unconnected-(U1B-NC-PadB5)") (class "Default")
      (node (ref "U1") (pin "B5") (pinfunction "NC_B5") (pintype "passive+no_connect"))
    )
    (net (code "23") (name "unconnected-(U1B-NC-PadB6)") (class "Default")
      (node (ref "U1") (pin "B6") (pinfunction "NC_B6") (pintype "passive+no_connect"))
    )
    (net (code "24") (name "unconnected-(U1B-NC-PadB7)") (class "Default")
      (node (ref "U1") (pin "B7") (pinfunction "NC_B7") (pintype "passive+no_connect"))
    )
    (net (code "25") (name "unconnected-(U1B-NC-PadB8)") (class "Default")
      (node (ref "U1") (pin "B8") (pinfunction "NC_B8") (pintype "passive+no_connect"))
    )
    (net (code "26") (name "unconnected-(U1B-NC-PadB9)") (class "Default")
      (node (ref "U1") (pin "B9") (pinfunction "NC_B9") (pintype "passive+no_connect"))
    )
    (net (code "27") (name "unconnected-(U1B-NC-PadB10)") (class "Default")
      (node (ref "U1") (pin "B10") (pinfunction "NC_B10") (pintype "passive+no_connect"))
    )
    (net (code "28") (name "unconnected-(U1B-NC-PadB11)") (class "Default")
      (node (ref "U1") (pin "B11") (pinfunction "NC_B11") (pintype "passive+no_connect"))
    )
    (net (code "29") (name "unconnected-(U1B-NC-PadB12)") (class "Default")
      (node (ref "U1") (pin "B12") (pinfunction "NC_B12") (pintype "passive+no_connect"))
    )
    (net (code "30") (name "unconnected-(U1B-NC-PadB13)") (class "Default")
      (node (ref "U1") (pin "B13") (pinfunction "NC_B13") (pintype "passive+no_connect"))
    )
    (net (code "31") (name "unconnected-(U1B-NC-PadB14)") (class "Default")
      (node (ref "U1") (pin "B14") (pinfunction "NC_B14") (pintype "passive+no_connect"))
    )
    (net (code "32") (name "unconnected-(U1B-NC-PadB15)") (class "Default")
      (node (ref "U1") (pin "B15") (pinfunction "NC_B15") (pintype "passive+no_connect"))
    )
    (net (code "33") (name "unconnected-(U1B-NC-PadB16)") (class "Default")
      (node (ref "U1") (pin "B16") (pinfunction "NC_B16") (pintype "passive+no_connect"))
    )
    (net (code "34") (name "unconnected-(U1B-NC-PadB17)") (class "Default")
      (node (ref "U1") (pin "B17") (pinfunction "NC_B17") (pintype "passive+no_connect"))
    )
    (net (code "35") (name "unconnected-(U1B-NC-PadB18)") (class "Default")
      (node (ref "U1") (pin "B18") (pinfunction "NC_B18") (pintype "passive+no_connect"))
    )
    (net (code "36") (name "unconnected-(U1B-NC-PadB19)") (class "Default")
      (node (ref "U1") (pin "B19") (pinfunction "NC_B19") (pintype "passive+no_connect"))
    )
    (net (code "37") (name "unconnected-(U1B-NC-PadB20)") (class "Default")
      (node (ref "U1") (pin "B20") (pinfunction "NC_B20") (pintype "passive+no_connect"))
    )
    (net (code "38") (name "unconnected-(U1B-NC-PadC2)") (class "Default")
      (node (ref "U1") (pin "C2") (pinfunction "NC_C2") (pintype "passive+no_connect"))
    )
    (net (code "39") (name "unconnected-(U1B-NC-PadC20)") (class "Default")
      (node (ref "U1") (pin "C20") (pinfunction "NC_C20") (pintype "passive+no_connect"))
    )
    (net (code "40") (name "unconnected-(U1B-NC-PadD2)") (class "Default")
      (node (ref "U1") (pin "D2") (pinfunction "NC_D2") (pintype "passive+no_connect"))
    )
    (net (code "41") (name "unconnected-(U1B-NC-PadD20)") (class "Default")
      (node (ref "U1") (pin "D20") (pinfunction "NC_D20") (pintype "passive+no_connect"))
    )
    (net (code "42") (name "unconnected-(U1B-NC-PadD21)") (class "Default")
      (node (ref "U1") (pin "D21") (pinfunction "NC_D21") (pintype "passive+no_connect"))
    )
    (net (code "43") (name "unconnected-(U1B-NC-PadE2)") (class "Default")
      (node (ref "U1") (pin "E2") (pinfunction "NC_E2") (pintype "passive+no_connect"))
    )
    (net (code "44") (name "unconnected-(U1B-NC-PadE20)") (class "Default")
      (node (ref "U1") (pin "E20") (pinfunction "NC_E20") (pintype "passive+no_connect"))
    )
    (net (code "45") (name "unconnected-(U1B-NC-PadE21)") (class "Default")
      (node (ref "U1") (pin "E21") (pinfunction "NC_E21") (pintype "passive+no_connect"))
    )
    (net (code "46") (name "unconnected-(U1B-NC-PadF2)") (class "Default")
      (node (ref "U1") (pin "F2") (pinfunction "NC_F2") (pintype "passive+no_connect"))
    )
    (net (code "47") (name "unconnected-(U1B-NC-PadF20)") (class "Default")
      (node (ref "U1") (pin "F20") (pinfunction "NC_F20") (pintype "passive+no_connect"))
    )
    (net (code "48") (name "unconnected-(U1B-NC-PadF21)") (class "Default")
      (node (ref "U1") (pin "F21") (pinfunction "NC_F21") (pintype "passive+no_connect"))
    )
    (net (code "49") (name "unconnected-(U1B-NC-PadG2)") (class "Default")
      (node (ref "U1") (pin "G2") (pinfunction "NC_G2") (pintype "passive+no_connect"))
    )
    (net (code "50") (name "unconnected-(U1B-NC-PadG20)") (class "Default")
      (node (ref "U1") (pin "G20") (pinfunction "NC_G20") (pintype "passive+no_connect"))
    )
    (net (code "51") (name "unconnected-(U1B-NC-PadH2)") (class "Default")
      (node (ref "U1") (pin "H2") (pinfunction "NC_H2") (pintype "passive+no_connect"))
    )
    (net (code "52") (name "unconnected-(U1B-NC-PadH20)") (class "Default")
      (node (ref "U1") (pin "H20") (pinfunction "NC_H20") (pintype "passive+no_connect"))
    )
    (net (code "53") (name "unconnected-(U1B-NC-PadJ2)") (class "Default")
      (node (ref "U1") (pin "J2") (pinfunction "NC_J2") (pintype "passive+no_connect"))
    )
    (net (code "54") (name "unconnected-(U1B-NC-PadY7)") (class "Default")
      (node (ref "U1") (pin "Y7") (pinfunction "NC_Y7") (pintype "passive+no_connect"))
    )
    (net (code "55") (name "unconnected-(U1B-NC-PadY10)") (class "Default")
      (node (ref "U1") (pin "Y10") (pinfunction "NC_Y10") (pintype "passive+no_connect"))
    )
    (net (code "56") (name "unconnected-(U1B-NC-PadY11)") (class "Default")
      (node (ref "U1") (pin "Y11") (pinfunction "NC_Y11") (pintype "passive+no_connect"))
    )
  )
)
